# DEV_Board.net
KiCad netlist of a schematic drawn in Altium Designer
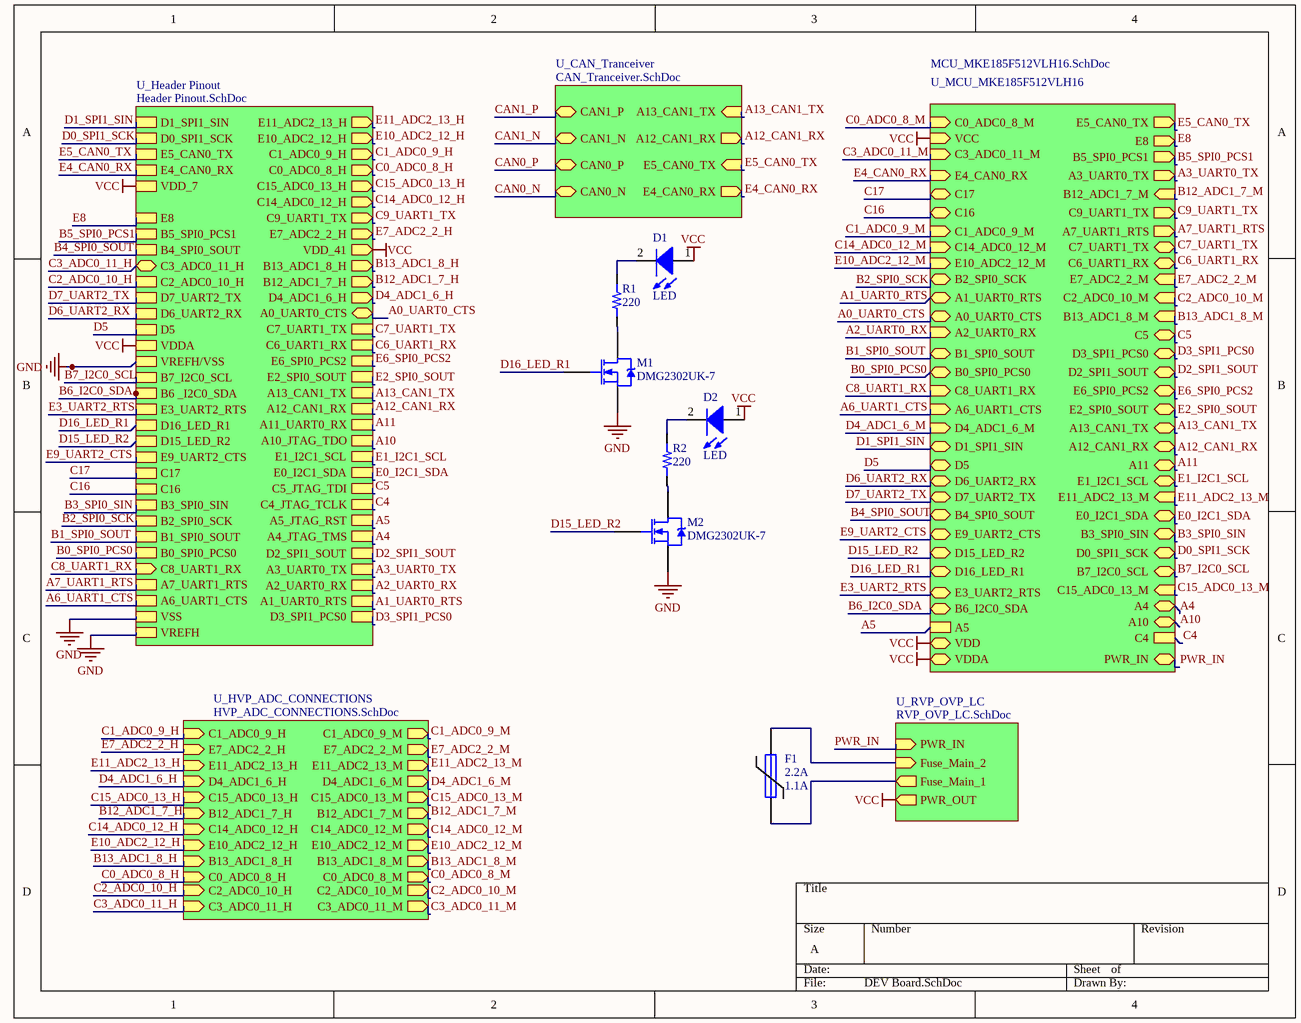
[diagram p0: DEV Board.SchDoc]

(export (version "E")
  (design (tool "Eeschema 10.0.6"))
  (components
    (comp (ref "D1") (value "LED") (footprint "0805_LED") (libsource (lib "Altium-Lib") (part "LED")))
    (comp (ref "D2") (value "LED") (footprint "0805_LED") (libsource (lib "Altium-Lib") (part "LED")))
    (comp (ref "F1")
      (value "2.2A")
      (footprint "PIN-W2/E2.8")
      (description "Fuse")
      (fields
        (field (name "I_HOLD") "1.1A")
        (field (name "MFRPARTNO") "1206L110/12SLYR")
        (field (name "PUBLISHER") "Altium Limited")
      )
      (libsource (lib "Altium-Lib") (part "PTC Fuse"))
    )
    (comp (ref "M1")
      (value "DMG2302UK-7")
      (footprint "SOT23-3")
      (description "MOSFET N-CHANNEL 30V 5A SOT23")
      (fields (field (name "CREATED_BY") "Angel"))
      (libsource (lib "Altium-Lib") (part "DMG2302UK-7"))
    )
    (comp (ref "M2")
      (value "DMG2302UK-7")
      (footprint "SOT23-3")
      (description "MOSFET N-CHANNEL 30V 5A SOT23")
      (fields (field (name "CREATED_BY") "Angel"))
      (libsource (lib "Altium-Lib") (part "DMG2302UK-7"))
    )
    (comp (ref "R1")
      (value "220")
      (footprint "RES 0402/1005")
      (fields
        (field (name "TOLERANCE") "1%")
        (field (name "POWER") "1/10W")
        (field (name "Comment") "Resistor 220 0402 1/10W 1%")
        (field (name "CREATED_BY") "Nick Mah")
      )
      (libsource (lib "Altium-Lib") (part "Resistor"))
    )
    (comp (ref "R2")
      (value "220")
      (footprint "RES 0402/1005")
      (fields
        (field (name "TOLERANCE") "1%")
        (field (name "POWER") "1/10W")
        (field (name "Comment") "Resistor 220 0402 1/10W 1%")
        (field (name "CREATED_BY") "Nick Mah")
      )
      (libsource (lib "Altium-Lib") (part "Resistor"))
    )
  )
  (nets
    (net (code "59") (name "/D15_LED_R2") (class "Default")
      (node (ref "M2") (pin "1") (pinfunction "G_1") (pintype "passive"))
    )
    (net (code "60") (name "/D16_LED_R1") (class "Default")
      (node (ref "M1") (pin "1") (pinfunction "G_1") (pintype "passive"))
    )
    (net (code "76") (name "/Fuse_Main_1") (class "Default")
      (node (ref "F1") (pin "1") (pinfunction "1_1") (pintype "passive"))
    )
    (net (code "77") (name "/Fuse_Main_2") (class "Default")
      (node (ref "F1") (pin "2") (pinfunction "2_2") (pintype "passive"))
    )
    (net (code "79") (name "GND") (class "Default")
      (node (ref "M1") (pin "2") (pinfunction "S_2") (pintype "passive"))
      (node (ref "M2") (pin "2") (pinfunction "S_2") (pintype "passive"))
    )
    (net (code "80") (name "Net-(D1-K)") (class "Default")
      (node (ref "D1") (pin "2") (pinfunction "K_2") (pintype "passive"))
      (node (ref "R1") (pin "2") (pinfunction "2_2") (pintype "passive"))
    )
    (net (code "81") (name "Net-(D2-K)") (class "Default")
      (node (ref "D2") (pin "2") (pinfunction "K_2") (pintype "passive"))
      (node (ref "R2") (pin "2") (pinfunction "2_2") (pintype "passive"))
    )
    (net (code "82") (name "Net-(M1-D)") (class "Default")
      (node (ref "M1") (pin "3") (pinfunction "D_3") (pintype "passive"))
      (node (ref "R1") (pin "1") (pinfunction "1_1") (pintype "passive"))
    )
    (net (code "83") (name "Net-(M2-D)") (class "Default")
      (node (ref "M2") (pin "3") (pinfunction "D_3") (pintype "passive"))
      (node (ref "R2") (pin "1") (pinfunction "1_1") (pintype "passive"))
    )
    (net (code "84") (name "VCC") (class "Default")
      (node (ref "D1") (pin "1") (pinfunction "A_1") (pintype "passive"))
      (node (ref "D2") (pin "1") (pinfunction "A_1") (pintype "passive"))
    )
  )
)
